# Supply.net
KiCad netlist of a schematic drawn in Altium Designer
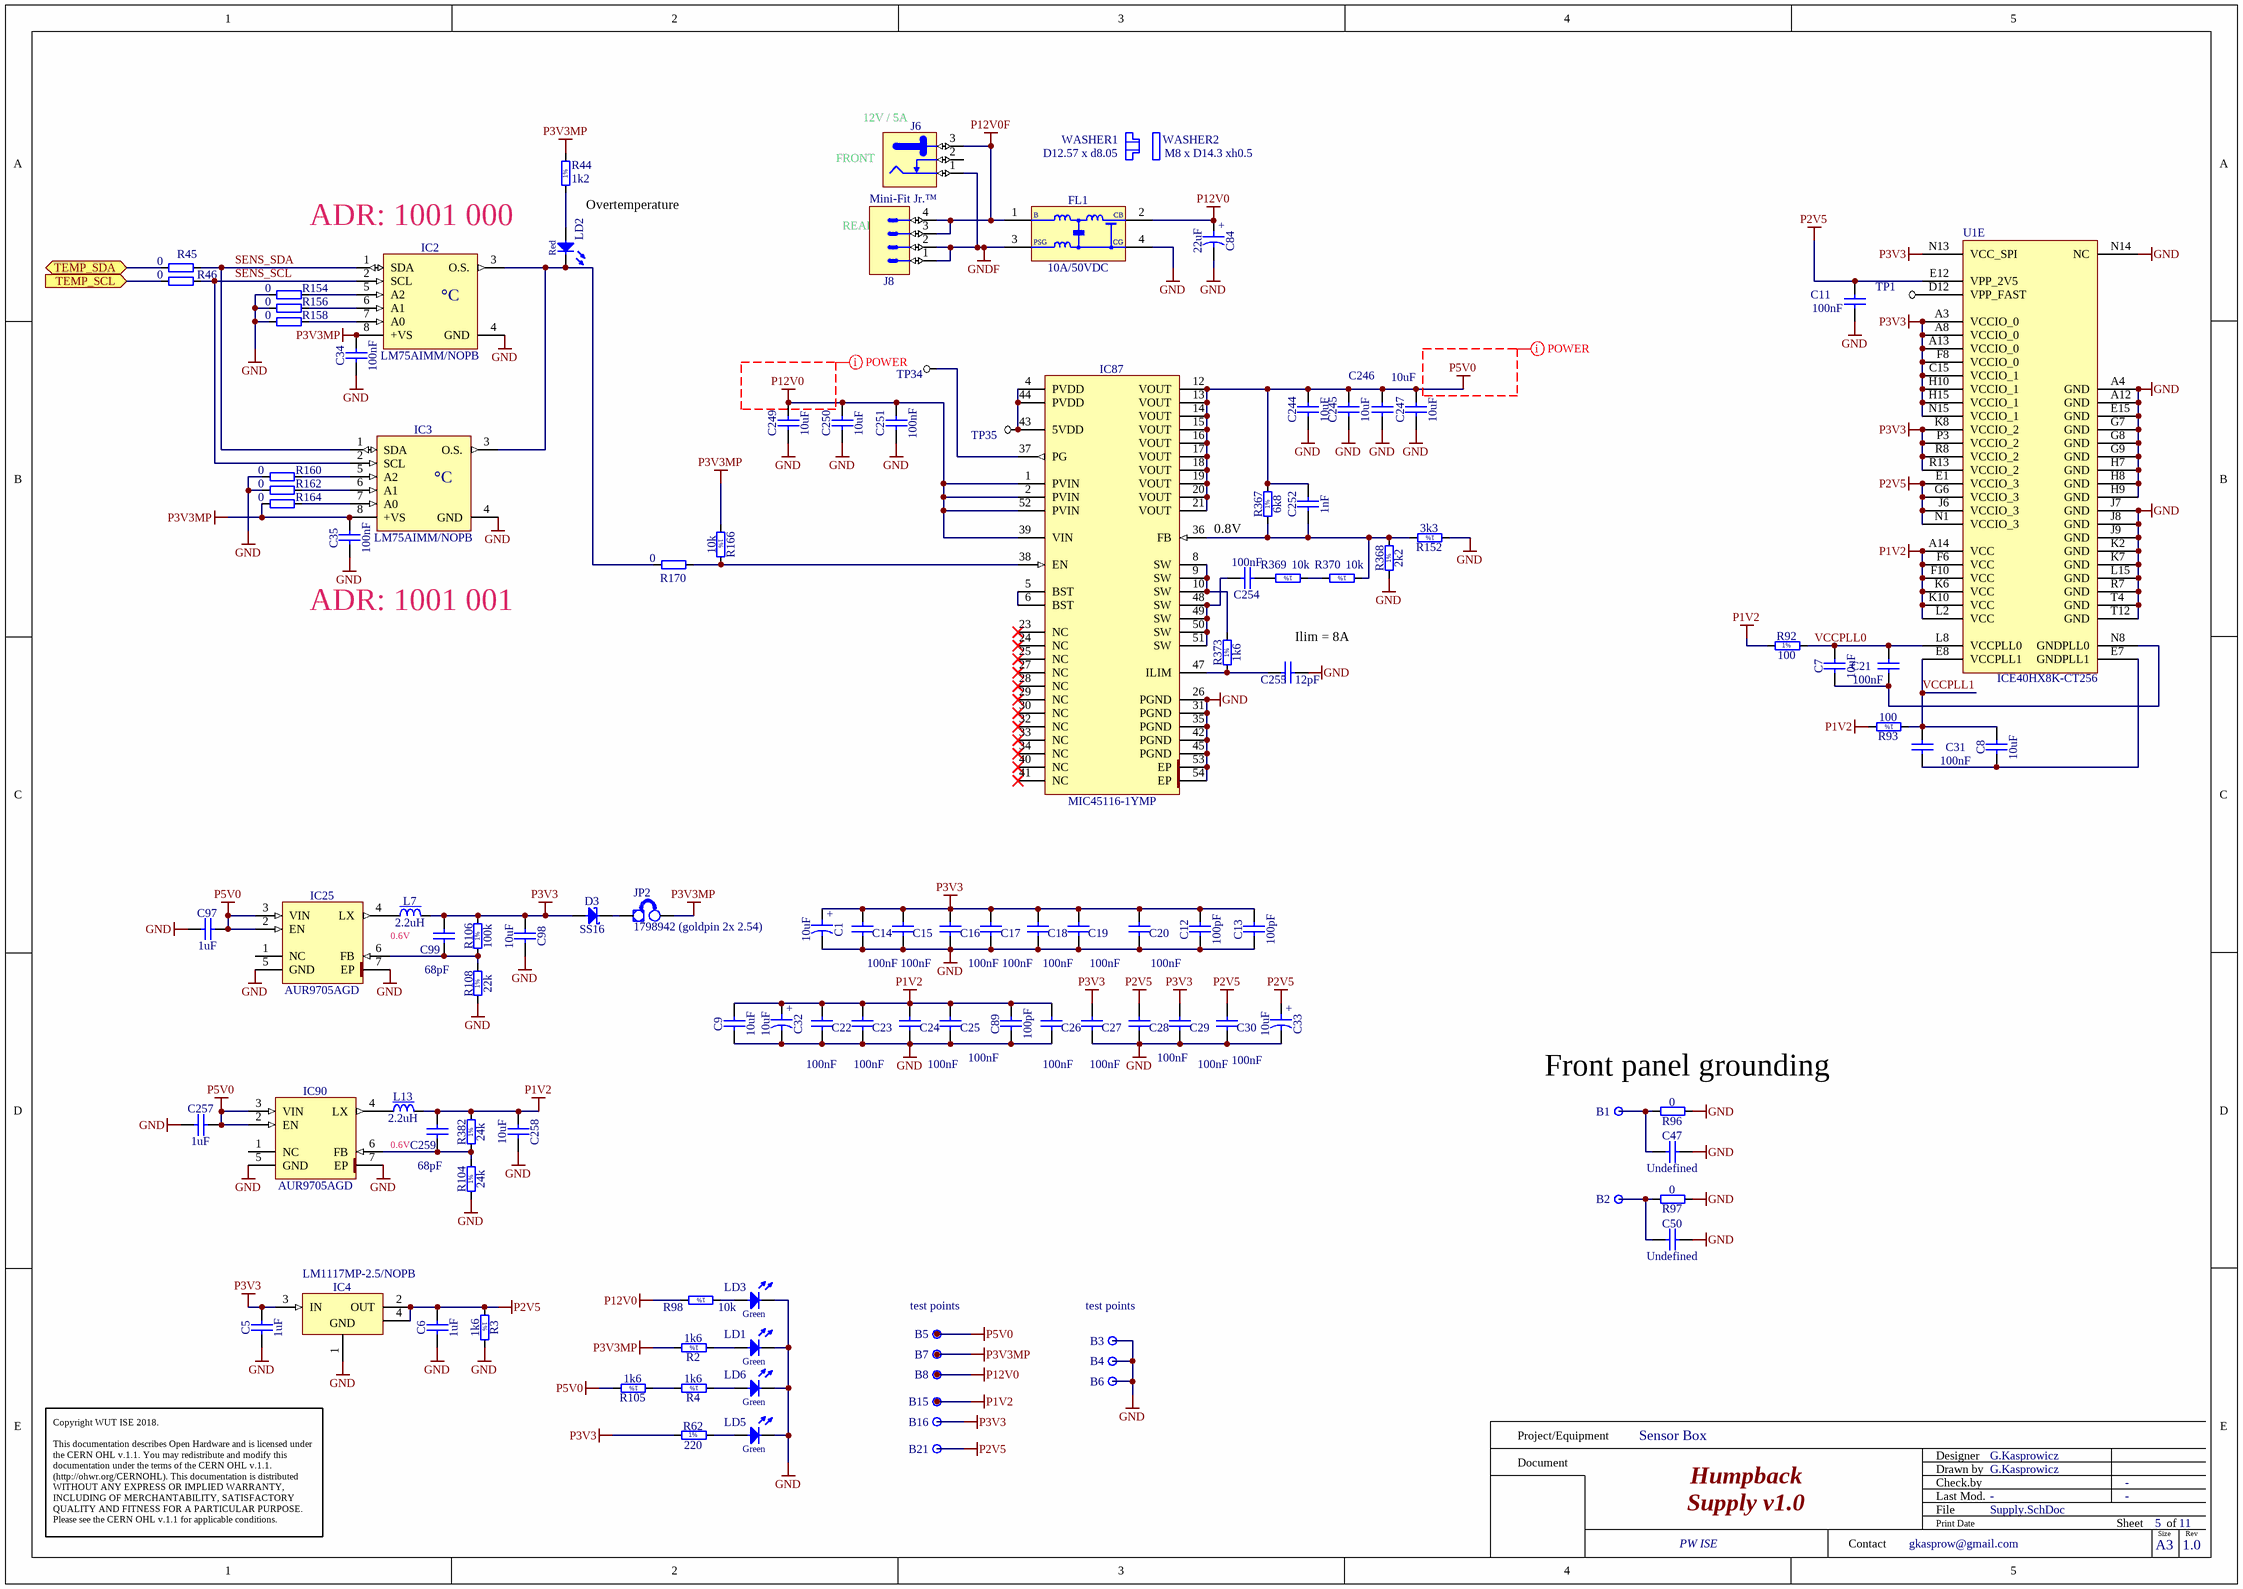
[diagram p0: Supply.SchDoc]

(export (version "E")
  (design (tool "Eeschema 10.0.6"))
  (components
    (comp (ref "B1")
      (value "Plated Hole")
      (footprint "MTG270_500")
      (description "Single Terminal Socket")
      (fields (field (name "PART NUMBER") "PLATED_HOLE2.7_PAD5.0") (field (name "AUTHOR") "CERN DEM JMW"))
      (libsource (lib "Eletro-mechanical") (part "Single Terminal Socket"))
    )
    (comp (ref "B2")
      (value "Plated Hole")
      (footprint "MTG270_500")
      (description "Single Terminal Socket")
      (fields (field (name "PART NUMBER") "PLATED_HOLE2.7_PAD5.0") (field (name "AUTHOR") "CERN DEM JMW"))
      (libsource (lib "Eletro-mechanical") (part "Single Terminal Socket"))
    )
    (comp (ref "B3")
      (value "Plated Hole")
      (footprint "c130h60")
      (description "Single Terminal Socket")
      (fields (field (name "PART NUMBER") "PLATED_HOLE0.6_PAD1.3") (field (name "AUTHOR") "CERN DEM MR"))
      (libsource (lib "Eletro-mechanical") (part "Single Terminal Socket"))
    )
    (comp (ref "B4")
      (value "Plated Hole")
      (footprint "c130h60")
      (description "Single Terminal Socket")
      (fields (field (name "PART NUMBER") "PLATED_HOLE0.6_PAD1.3") (field (name "AUTHOR") "CERN DEM MR"))
      (libsource (lib "Eletro-mechanical") (part "Single Terminal Socket"))
    )
    (comp (ref "B5")
      (value "Plated Hole")
      (footprint "c130h60")
      (description "Single Terminal Socket")
      (fields (field (name "PART NUMBER") "PLATED_HOLE0.6_PAD1.3") (field (name "AUTHOR") "CERN DEM MR"))
      (libsource (lib "Eletro-mechanical") (part "Single Terminal Socket"))
    )
    (comp (ref "B6")
      (value "Plated Hole")
      (footprint "c130h60")
      (description "Single Terminal Socket")
      (fields (field (name "PART NUMBER") "PLATED_HOLE0.6_PAD1.3") (field (name "AUTHOR") "CERN DEM MR"))
      (libsource (lib "Eletro-mechanical") (part "Single Terminal Socket"))
    )
    (comp (ref "B7")
      (value "Plated Hole")
      (footprint "c130h60")
      (description "Single Terminal Socket")
      (fields (field (name "PART NUMBER") "PLATED_HOLE0.6_PAD1.3") (field (name "AUTHOR") "CERN DEM MR"))
      (libsource (lib "Eletro-mechanical") (part "Single Terminal Socket"))
    )
    (comp (ref "B8")
      (value "Plated Hole")
      (footprint "c130h60")
      (description "Single Terminal Socket")
      (fields (field (name "PART NUMBER") "PLATED_HOLE0.6_PAD1.3") (field (name "AUTHOR") "CERN DEM MR"))
      (libsource (lib "Eletro-mechanical") (part "Single Terminal Socket"))
    )
    (comp (ref "B15")
      (value "Plated Hole")
      (footprint "c130h60")
      (description "Single Terminal Socket")
      (fields (field (name "PART NUMBER") "PLATED_HOLE0.6_PAD1.3") (field (name "AUTHOR") "CERN DEM MR"))
      (libsource (lib "Eletro-mechanical") (part "Single Terminal Socket"))
    )
    (comp (ref "B16")
      (value "Plated Hole")
      (footprint "c130h60")
      (description "Single Terminal Socket")
      (fields (field (name "PART NUMBER") "PLATED_HOLE0.6_PAD1.3") (field (name "AUTHOR") "CERN DEM MR"))
      (libsource (lib "Eletro-mechanical") (part "Single Terminal Socket"))
    )
    (comp (ref "B21")
      (value "Plated Hole")
      (footprint "c130h60")
      (description "Single Terminal Socket")
      (fields (field (name "PART NUMBER") "PLATED_HOLE0.6_PAD1.3") (field (name "AUTHOR") "CERN DEM MR"))
      (libsource (lib "Eletro-mechanical") (part "Single Terminal Socket"))
    )
    (comp (ref "C1")
      (value "10uF")
      (footprint "CAPAE430X540N")
      (description "Polarised capacitor")
      (fields
        (field (name "PART NUMBER") "CAE430-540_10UF_16V_20%")
        (field (name "VOLTAGE") "16V")
        (field (name "AUTHOR") "CERN DEM JLC")
      )
      (libsource (lib "Capacitors") (part "Capacitor - polarized"))
    )
    (comp (ref "C5")
      (value "1uF")
      (footprint "CAPC1608X87N")
      (description "Non-polarised capacitor")
      (fields
        (field (name "PART NUMBER") "CC0603_1UF_25V_10%_X7R")
        (field (name "VOLTAGE") "25V")
        (field (name "AUTHOR") "CERN DEM JLC")
      )
      (libsource (lib "Capacitors") (part "Capacitor - non polarized"))
    )
    (comp (ref "C6")
      (value "1uF")
      (footprint "CAPC1608X87N")
      (description "Non-polarised capacitor")
      (fields
        (field (name "PART NUMBER") "CC0603_1UF_25V_10%_X7R")
        (field (name "VOLTAGE") "25V")
        (field (name "AUTHOR") "CERN DEM JLC")
      )
      (libsource (lib "Capacitors") (part "Capacitor - non polarized"))
    )
    (comp (ref "C7")
      (value "10uF")
      (footprint "CAPC1005X70N")
      (description "Non-polarised capacitor")
      (fields
        (field (name "PART NUMBER") "CC0402_10UF_6.3V_20%_X5R")
        (field (name "VOLTAGE") "6.3V")
        (field (name "AUTHOR") "CERN DEM JLC")
      )
      (libsource (lib "Capacitors") (part "Capacitor - non polarized"))
    )
    (comp (ref "C8")
      (value "10uF")
      (footprint "CAPC1005X70N")
      (description "Non-polarised capacitor")
      (fields
        (field (name "PART NUMBER") "CC0402_10UF_6.3V_20%_X5R")
        (field (name "VOLTAGE") "6.3V")
        (field (name "AUTHOR") "CERN DEM JLC")
      )
      (libsource (lib "Capacitors") (part "Capacitor - non polarized"))
    )
    (comp (ref "C9")
      (value "10uF")
      (footprint "CAPC2012X135N")
      (description "Non-polarised capacitor")
      (fields
        (field (name "PART NUMBER") "CC0805_10UF_16V_10%_X5R")
        (field (name "VOLTAGE") "16V")
        (field (name "AUTHOR") "CERN DEM JLC")
      )
      (libsource (lib "Capacitors") (part "Capacitor - non polarized"))
    )
    (comp (ref "C11")
      (value "100nF")
      (footprint "CAPC1005X55N")
      (description "Non-polarised capacitor")
      (fields
        (field (name "PART NUMBER") "CC0402_100NF_16V_10%_X5R")
        (field (name "VOLTAGE") "16V")
        (field (name "AUTHOR") "CERN DEM JLC")
      )
      (libsource (lib "Capacitors") (part "Capacitor - non polarized"))
    )
    (comp (ref "C12")
      (value "100pF")
      (footprint "CAPC1608X87N")
      (description "Non-polarised capacitor")
      (fields
        (field (name "PART NUMBER") "CC0603_100PF_50V_10%_X7R")
        (field (name "VOLTAGE") "50V")
        (field (name "AUTHOR") "CERN DEM JLC")
      )
      (libsource (lib "Capacitors") (part "Capacitor - non polarized"))
    )
    (comp (ref "C13")
      (value "100pF")
      (footprint "CAPC1608X87N")
      (description "Non-polarised capacitor")
      (fields
        (field (name "PART NUMBER") "CC0603_100PF_50V_10%_X7R")
        (field (name "VOLTAGE") "50V")
        (field (name "AUTHOR") "CERN DEM JLC")
      )
      (libsource (lib "Capacitors") (part "Capacitor - non polarized"))
    )
    (comp (ref "C14")
      (value "100nF")
      (footprint "CAPC1005X55N")
      (description "Non-polarised capacitor")
      (fields
        (field (name "PART NUMBER") "CC0402_100NF_16V_10%_X5R")
        (field (name "VOLTAGE") "16V")
        (field (name "AUTHOR") "CERN DEM JLC")
      )
      (libsource (lib "Capacitors") (part "Capacitor - non polarized"))
    )
    (comp (ref "C15")
      (value "100nF")
      (footprint "CAPC1005X55N")
      (description "Non-polarised capacitor")
      (fields
        (field (name "PART NUMBER") "CC0402_100NF_16V_10%_X5R")
        (field (name "VOLTAGE") "16V")
        (field (name "AUTHOR") "CERN DEM JLC")
      )
      (libsource (lib "Capacitors") (part "Capacitor - non polarized"))
    )
    (comp (ref "C16")
      (value "100nF")
      (footprint "CAPC1005X55N")
      (description "Non-polarised capacitor")
      (fields
        (field (name "PART NUMBER") "CC0402_100NF_16V_10%_X5R")
        (field (name "VOLTAGE") "16V")
        (field (name "AUTHOR") "CERN DEM JLC")
      )
      (libsource (lib "Capacitors") (part "Capacitor - non polarized"))
    )
    (comp (ref "C17")
      (value "100nF")
      (footprint "CAPC1005X55N")
      (description "Non-polarised capacitor")
      (fields
        (field (name "PART NUMBER") "CC0402_100NF_16V_10%_X5R")
        (field (name "VOLTAGE") "16V")
        (field (name "AUTHOR") "CERN DEM JLC")
      )
      (libsource (lib "Capacitors") (part "Capacitor - non polarized"))
    )
    (comp (ref "C18")
      (value "100nF")
      (footprint "CAPC1005X55N")
      (description "Non-polarised capacitor")
      (fields
        (field (name "PART NUMBER") "CC0402_100NF_16V_10%_X5R")
        (field (name "VOLTAGE") "16V")
        (field (name "AUTHOR") "CERN DEM JLC")
      )
      (libsource (lib "Capacitors") (part "Capacitor - non polarized"))
    )
    (comp (ref "C19")
      (value "100nF")
      (footprint "CAPC1005X55N")
      (description "Non-polarised capacitor")
      (fields
        (field (name "PART NUMBER") "CC0402_100NF_16V_10%_X5R")
        (field (name "VOLTAGE") "16V")
        (field (name "AUTHOR") "CERN DEM JLC")
      )
      (libsource (lib "Capacitors") (part "Capacitor - non polarized"))
    )
    (comp (ref "C20")
      (value "100nF")
      (footprint "CAPC1005X55N")
      (description "Non-polarised capacitor")
      (fields
        (field (name "PART NUMBER") "CC0402_100NF_16V_10%_X5R")
        (field (name "VOLTAGE") "16V")
        (field (name "AUTHOR") "CERN DEM JLC")
      )
      (libsource (lib "Capacitors") (part "Capacitor - non polarized"))
    )
    (comp (ref "C21")
      (value "100nF")
      (footprint "CAPC1005X55N")
      (description "Non-polarised capacitor")
      (fields
        (field (name "PART NUMBER") "CC0402_100NF_16V_10%_X5R")
        (field (name "VOLTAGE") "16V")
        (field (name "AUTHOR") "CERN DEM JLC")
      )
      (libsource (lib "Capacitors") (part "Capacitor - non polarized"))
    )
    (comp (ref "C22")
      (value "100nF")
      (footprint "CAPC1005X55N")
      (description "Non-polarised capacitor")
      (fields
        (field (name "PART NUMBER") "CC0402_100NF_16V_10%_X5R")
        (field (name "VOLTAGE") "16V")
        (field (name "AUTHOR") "CERN DEM JLC")
      )
      (libsource (lib "Capacitors") (part "Capacitor - non polarized"))
    )
    (comp (ref "C23")
      (value "100nF")
      (footprint "CAPC1005X55N")
      (description "Non-polarised capacitor")
      (fields
        (field (name "PART NUMBER") "CC0402_100NF_16V_10%_X5R")
        (field (name "VOLTAGE") "16V")
        (field (name "AUTHOR") "CERN DEM JLC")
      )
      (libsource (lib "Capacitors") (part "Capacitor - non polarized"))
    )
    (comp (ref "C24")
      (value "100nF")
      (footprint "CAPC1005X55N")
      (description "Non-polarised capacitor")
      (fields
        (field (name "PART NUMBER") "CC0402_100NF_16V_10%_X5R")
        (field (name "VOLTAGE") "16V")
        (field (name "AUTHOR") "CERN DEM JLC")
      )
      (libsource (lib "Capacitors") (part "Capacitor - non polarized"))
    )
    (comp (ref "C25")
      (value "100nF")
      (footprint "CAPC1005X55N")
      (description "Non-polarised capacitor")
      (fields
        (field (name "PART NUMBER") "CC0402_100NF_16V_10%_X5R")
        (field (name "VOLTAGE") "16V")
        (field (name "AUTHOR") "CERN DEM JLC")
      )
      (libsource (lib "Capacitors") (part "Capacitor - non polarized"))
    )
    (comp (ref "C26")
      (value "100nF")
      (footprint "CAPC1005X55N")
      (description "Non-polarised capacitor")
      (fields
        (field (name "PART NUMBER") "CC0402_100NF_16V_10%_X5R")
        (field (name "VOLTAGE") "16V")
        (field (name "AUTHOR") "CERN DEM JLC")
      )
      (libsource (lib "Capacitors") (part "Capacitor - non polarized"))
    )
    (comp (ref "C27")
      (value "100nF")
      (footprint "CAPC1005X55N")
      (description "Non-polarised capacitor")
      (fields
        (field (name "PART NUMBER") "CC0402_100NF_16V_10%_X5R")
        (field (name "VOLTAGE") "16V")
        (field (name "AUTHOR") "CERN DEM JLC")
      )
      (libsource (lib "Capacitors") (part "Capacitor - non polarized"))
    )
    (comp (ref "C28")
      (value "100nF")
      (footprint "CAPC1005X55N")
      (description "Non-polarised capacitor")
      (fields
        (field (name "PART NUMBER") "CC0402_100NF_16V_10%_X5R")
        (field (name "VOLTAGE") "16V")
        (field (name "AUTHOR") "CERN DEM JLC")
      )
      (libsource (lib "Capacitors") (part "Capacitor - non polarized"))
    )
    (comp (ref "C29")
      (value "100nF")
      (footprint "CAPC1005X55N")
      (description "Non-polarised capacitor")
      (fields
        (field (name "PART NUMBER") "CC0402_100NF_16V_10%_X5R")
        (field (name "VOLTAGE") "16V")
        (field (name "AUTHOR") "CERN DEM JLC")
      )
      (libsource (lib "Capacitors") (part "Capacitor - non polarized"))
    )
    (comp (ref "C30")
      (value "100nF")
      (footprint "CAPC1005X55N")
      (description "Non-polarised capacitor")
      (fields
        (field (name "PART NUMBER") "CC0402_100NF_16V_10%_X5R")
        (field (name "VOLTAGE") "16V")
        (field (name "AUTHOR") "CERN DEM JLC")
      )
      (libsource (lib "Capacitors") (part "Capacitor - non polarized"))
    )
    (comp (ref "C31")
      (value "100nF")
      (footprint "CAPC1005X55N")
      (description "Non-polarised capacitor")
      (fields
        (field (name "PART NUMBER") "CC0402_100NF_16V_10%_X5R")
        (field (name "VOLTAGE") "16V")
        (field (name "AUTHOR") "CERN DEM JLC")
      )
      (libsource (lib "Capacitors") (part "Capacitor - non polarized"))
    )
    (comp (ref "C32")
      (value "10uF")
      (footprint "CAPAE430X540N")
      (description "Polarised capacitor")
      (fields
        (field (name "PART NUMBER") "CAE430-540_10UF_16V_20%")
        (field (name "VOLTAGE") "16V")
        (field (name "AUTHOR") "CERN DEM JLC")
      )
      (libsource (lib "Capacitors") (part "Capacitor - polarized"))
    )
    (comp (ref "C33")
      (value "10uF")
      (footprint "CAPAE430X540N")
      (description "Polarised capacitor")
      (fields
        (field (name "PART NUMBER") "CAE430-540_10UF_16V_20%")
        (field (name "VOLTAGE") "16V")
        (field (name "AUTHOR") "CERN DEM JLC")
      )
      (libsource (lib "Capacitors") (part "Capacitor - polarized"))
    )
    (comp (ref "C34")
      (value "100nF")
      (footprint "CAPC1005X55N")
      (description "Non-polarised capacitor")
      (fields
        (field (name "PART NUMBER") "CC0402_100NF_16V_10%_X5R")
        (field (name "VOLTAGE") "16V")
        (field (name "AUTHOR") "CERN DEM JLC")
      )
      (libsource (lib "Capacitors") (part "Capacitor - non polarized"))
    )
    (comp (ref "C35")
      (value "100nF")
      (footprint "CAPC1005X55N")
      (description "Non-polarised capacitor")
      (fields
        (field (name "PART NUMBER") "CC0402_100NF_16V_10%_X5R")
        (field (name "VOLTAGE") "16V")
        (field (name "AUTHOR") "CERN DEM JLC")
      )
      (libsource (lib "Capacitors") (part "Capacitor - non polarized"))
    )
    (comp (ref "C47")
      (value "Undefined")
      (footprint "CAPC2012X135N")
      (description "Non-polarised capacitor")
      (fields (field (name "PART NUMBER") "CC0805_NO-VALUE") (field (name "AUTHOR") "CERN DEM JLC"))
      (libsource (lib "Capacitors") (part "Capacitor - non polarized"))
    )
    (comp (ref "C50")
      (value "Undefined")
      (footprint "CAPC2012X135N")
      (description "Non-polarised capacitor")
      (fields (field (name "PART NUMBER") "CC0805_NO-VALUE") (field (name "AUTHOR") "CERN DEM JLC"))
      (libsource (lib "Capacitors") (part "Capacitor - non polarized"))
    )
    (comp (ref "C84")
      (value "22uF")
      (footprint "CAPAE530X540N")
      (description "Polarised capacitor")
      (fields
        (field (name "PART NUMBER") "CAE530-540_22UF_16V_20%")
        (field (name "VOLTAGE") "16V")
        (field (name "AUTHOR") "CERN DEM JLC")
      )
      (libsource (lib "Capacitors") (part "Capacitor - polarized"))
    )
    (comp (ref "C89")
      (value "100pF")
      (footprint "CAPC1608X87N")
      (description "Non-polarised capacitor")
      (fields
        (field (name "PART NUMBER") "CC0603_100PF_50V_10%_X7R")
        (field (name "VOLTAGE") "50V")
        (field (name "AUTHOR") "CERN DEM JLC")
      )
      (libsource (lib "Capacitors") (part "Capacitor - non polarized"))
    )
    (comp (ref "C97")
      (value "1uF")
      (footprint "CAPC1005X55N")
      (description "Non-polarised capacitor")
      (fields
        (field (name "PART NUMBER") "CC0402_1UF_16V_10%_X5R")
        (field (name "VOLTAGE") "16V")
        (field (name "AUTHOR") "CERN DEM JLC")
      )
      (libsource (lib "Capacitors") (part "Capacitor - non polarized"))
    )
    (comp (ref "C98")
      (value "10uF")
      (footprint "CAPC2012X135N")
      (description "Non-polarised capacitor")
      (fields
        (field (name "PART NUMBER") "CC0805_10UF_16V_10%_X5R")
        (field (name "VOLTAGE") "16V")
        (field (name "AUTHOR") "CERN DEM JLC")
      )
      (libsource (lib "Capacitors") (part "Capacitor - non polarized"))
    )
    (comp (ref "C99")
      (value "68pF")
      (footprint "CAPC1608X87N")
      (description "Non-polarised capacitor")
      (fields
        (field (name "PART NUMBER") "CC0603_68PF_50V_5%_NP0")
        (field (name "VOLTAGE") "50V")
        (field (name "AUTHOR") "CERN DEM JLC")
      )
      (libsource (lib "Capacitors") (part "Capacitor - non polarized"))
    )
    (comp (ref "C244")
      (value "10uF")
      (footprint "CAPC2012X135N")
      (description "Non-polarised capacitor")
      (fields
        (field (name "PART NUMBER") "CC0805_10UF_16V_10%_X5R")
        (field (name "VOLTAGE") "16V")
        (field (name "AUTHOR") "CERN DEM JLC")
      )
      (libsource (lib "Capacitors") (part "Capacitor - non polarized"))
    )
    (comp (ref "C245")
      (value "10uF")
      (footprint "CAPC2012X135N")
      (description "Non-polarised capacitor")
      (fields
        (field (name "PART NUMBER") "CC0805_10UF_16V_10%_X5R")
        (field (name "VOLTAGE") "16V")
        (field (name "AUTHOR") "CERN DEM JLC")
      )
      (libsource (lib "Capacitors") (part "Capacitor - non polarized"))
    )
    (comp (ref "C246")
      (value "10uF")
      (footprint "CAPC2012X135N")
      (description "Non-polarised capacitor")
      (fields
        (field (name "PART NUMBER") "CC0805_10UF_16V_10%_X5R")
        (field (name "VOLTAGE") "16V")
        (field (name "AUTHOR") "CERN DEM JLC")
      )
      (libsource (lib "Capacitors") (part "Capacitor - non polarized"))
    )
    (comp (ref "C247")
      (value "10uF")
      (footprint "CAPC2012X135N")
      (description "Non-polarised capacitor")
      (fields
        (field (name "PART NUMBER") "CC0805_10UF_16V_10%_X5R")
        (field (name "VOLTAGE") "16V")
        (field (name "AUTHOR") "CERN DEM JLC")
      )
      (libsource (lib "Capacitors") (part "Capacitor - non polarized"))
    )
    (comp (ref "C249")
      (value "10uF")
      (footprint "CAPC2012X135N")
      (description "Non-polarised capacitor")
      (fields
        (field (name "PART NUMBER") "CC0805_10UF_16V_10%_X5R")
        (field (name "VOLTAGE") "16V")
        (field (name "AUTHOR") "CERN DEM JLC")
      )
      (libsource (lib "Capacitors") (part "Capacitor - non polarized"))
    )
    (comp (ref "C250")
      (value "10uF")
      (footprint "CAPC2012X135N")
      (description "Non-polarised capacitor")
      (fields
        (field (name "PART NUMBER") "CC0805_10UF_16V_10%_X5R")
        (field (name "VOLTAGE") "16V")
        (field (name "AUTHOR") "CERN DEM JLC")
      )
      (libsource (lib "Capacitors") (part "Capacitor - non polarized"))
    )
    (comp (ref "C251")
      (value "100nF")
      (footprint "CAPC1005X55N")
      (description "Non-polarised capacitor")
      (fields
        (field (name "PART NUMBER") "CC0402_100NF_16V_10%_X5R")
        (field (name "VOLTAGE") "16V")
        (field (name "AUTHOR") "CERN DEM JLC")
      )
      (libsource (lib "Capacitors") (part "Capacitor - non polarized"))
    )
    (comp (ref "C252")
      (value "1nF")
      (footprint "CAPC1608X87N")
      (description "Non-polarised capacitor")
      (fields
        (field (name "PART NUMBER") "CC0603_1NF_100V_10%_X7R")
        (field (name "VOLTAGE") "100V")
        (field (name "AUTHOR") "CERN DEM JLC")
      )
      (libsource (lib "Capacitors") (part "Capacitor - non polarized"))
    )
    (comp (ref "C254")
      (value "100nF")
      (footprint "CAPC1005X55N")
      (description "Non-polarised capacitor")
      (fields
        (field (name "PART NUMBER") "CC0402_100NF_16V_10%_X5R")
        (field (name "VOLTAGE") "16V")
        (field (name "AUTHOR") "CERN DEM JLC")
      )
      (libsource (lib "Capacitors") (part "Capacitor - non polarized"))
    )
    (comp (ref "C255")
      (value "12pF")
      (footprint "CAPC1005X55N")
      (description "Non-polarised capacitor")
      (fields
        (field (name "PART NUMBER") "CC0402_12PF_50V_5%_C0G")
        (field (name "VOLTAGE") "50V")
        (field (name "AUTHOR") "CERN DEM JLC")
      )
      (libsource (lib "Capacitors") (part "Capacitor - non polarized"))
    )
    (comp (ref "C257")
      (value "1uF")
      (footprint "CAPC1005X55N")
      (description "Non-polarised capacitor")
      (fields
        (field (name "PART NUMBER") "CC0402_1UF_16V_10%_X5R")
        (field (name "VOLTAGE") "16V")
        (field (name "AUTHOR") "CERN DEM JLC")
      )
      (libsource (lib "Capacitors") (part "Capacitor - non polarized"))
    )
    (comp (ref "C258")
      (value "10uF")
      (footprint "CAPC2012X135N")
      (description "Non-polarised capacitor")
      (fields
        (field (name "PART NUMBER") "CC0805_10UF_16V_10%_X5R")
        (field (name "VOLTAGE") "16V")
        (field (name "AUTHOR") "CERN DEM JLC")
      )
      (libsource (lib "Capacitors") (part "Capacitor - non polarized"))
    )
    (comp (ref "C259")
      (value "68pF")
      (footprint "CAPC1608X87N")
      (description "Non-polarised capacitor")
      (fields
        (field (name "PART NUMBER") "CC0603_68PF_50V_5%_NP0")
        (field (name "VOLTAGE") "50V")
        (field (name "AUTHOR") "CERN DEM JLC")
      )
      (libsource (lib "Capacitors") (part "Capacitor - non polarized"))
    )
    (comp (ref "D3")
      (value "SS16")
      (footprint "DIOM5127X229N")
      (description "Schottky Diode")
      (fields
        (field (name "VOLTAGE") "60V")
        (field (name "POWER") "1A")
        (field (name "AUTHOR") "CERN DEM JLC")
      )
      (libsource (lib "ICs And Semiconductors") (part "Diode Schottky"))
    )
    (comp (ref "FL1")
      (value "10A/50VDC")
      (footprint "FIL_MURATA_BNX02")
      (description "Block Type EMIFIL (LC Combined)")
      (fields
        (field (name "PART NUMBER") "FIL_MURATA_BNX022-01L")
        (field (name "MANUFACTURER") "MURATA")
        (field (name "AUTHOR") "CERN DEM JLC")
      )
      (libsource (lib "Inductors & Transformers") (part "FIL_MURATA_BNX02"))
    )
    (comp (ref "IC2")
      (value "LM75AIMM/NOPB")
      (footprint "SOP65P490X109-8N")
      (description "Digital Temperature Sensor and Thermal Watchdog with Two-Wire Interface")
      (fields (field (name "MANUFACTURER") "TEXAS INSTRUMENTS") (field (name "AUTHOR") "CERN DEM JLC"))
      (libsource (lib "ICs And Semiconductors") (part "LM75"))
    )
    (comp (ref "IC3")
      (value "LM75AIMM/NOPB")
      (footprint "SOP65P490X109-8N")
      (description "Digital Temperature Sensor and Thermal Watchdog with Two-Wire Interface")
      (fields (field (name "MANUFACTURER") "TEXAS INSTRUMENTS") (field (name "AUTHOR") "CERN DEM JLC"))
      (libsource (lib "ICs And Semiconductors") (part "LM75"))
    )
    (comp (ref "IC4")
      (value "LM1117MP-2.5/NOPB")
      (footprint "SOT230P700X180-4N")
      (description "3-Terminal Regulator 1=GND 2=OUT 3=IN 4=OUT")
      (fields (field (name "MANUFACTURER") "TEXAS INSTRUMENTS") (field (name "AUTHOR") "CERN DEM JLC"))
      (libsource (lib "ICs And Semiconductors") (part "REG3+1 1GND-2OUT-3IN+4OUT"))
    )
    (comp (ref "IC25")
      (value "AUR9705AGD")
      (footprint "SON65P200X200X80-7N-R65X145")
      (description "0V to 6V Input, 1A, 1.5MHz, Step-Down DC-DC Converter")
      (fields (field (name "MANUFACTURER") "DIODES INCORPORATED") (field (name "AUTHOR") "CERN DEM MR"))
      (libsource (lib "ICs And Semiconductors") (part "AUR9705AGD"))
    )
    (comp (ref "IC87")
      (value "MIC45116-1YMP")
      (footprint "MICROCHIP_H3QFN88-52LD-PL-3")
      (description "0.8V to 85% PVIN (4.75-19V), 6A Synchronous Step-Down Regulator Module")
      (fields (field (name "MANUFACTURER") "MICROCHIP TECHNOLOGY") (field (name "AUTHOR") "CERN DEM JMW"))
      (libsource (lib "ICs And Semiconductors") (part "MIC45116"))
    )
    (comp (ref "IC90")
      (value "AUR9705AGD")
      (footprint "SON65P200X200X80-7N-R65X145")
      (description "0V to 6V Input, 1A, 1.5MHz, Step-Down DC-DC Converter")
      (fields (field (name "MANUFACTURER") "DIODES INCORPORATED") (field (name "AUTHOR") "CERN DEM MR"))
      (libsource (lib "ICs And Semiconductors") (part "AUR9705AGD"))
    )
    (comp (ref "J6")
      (value "Jack")
      (footprint "SWITCHCRAFT_L712RA")
      (description "24V /3. 5A, 2.1mm Diameter Pin, SMD DC Power Supply Connector With  Break Contact")
      (fields
        (field (name "PART NUMBER") "SWITCHCRAFT_L712RA")
        (field (name "MANUFACTURER") "SWITCHCRAFT")
        (field (name "AUTHOR") "GK")
      )
      (libsource (lib "LIBRARY_SCH") (part "CON_DC_5A_THT_RA"))
    )
    (comp (ref "J8")
      (value "Mini-Fit Jr.™")
      (footprint "MOLEX_39-30-0040")
      (description "Connector 4 Male")
      (fields
        (field (name "PART NUMBER") "MOLEX_39-30-0040")
        (field (name "FAMILY") "Mini-Fit Jr.™")
        (field (name "MANUFACTURER") "MOLEX")
        (field (name "AUTHOR") "CERN DEM JLC")
      )
      (libsource (lib "Connectors") (part "Connector 4 Male"))
    )
    (comp (ref "JP2")
      (value "1798942 (goldpin 2x 2.54)")
      (footprint "jump")
      (description "Jumper")
      (libsource (lib "LIBRARY_SCH") (part "JUMPER"))
    )
    (comp (ref "L7")
      (value "2.2uH")
      (footprint "IND_MURATA_LQH44PN_P0")
      (description "Inductor With Core")
      (fields
        (field (name "PART NUMBER") "IND_2.2UH_20%_MURATA_LQH44PN2R2MP0L")
        (field (name "POWER") "1.8A")
        (field (name "AUTHOR") "CERN DEM JLC")
      )
      (libsource (lib "Inductors & Transformers") (part "Inductor With Magnetic core"))
    )
    (comp (ref "L13")
      (value "2.2uH")
      (footprint "IND_MURATA_LQH44PN_P0")
      (description "Inductor With Core")
      (fields
        (field (name "PART NUMBER") "IND_2.2UH_20%_MURATA_LQH44PN2R2MP0L")
        (field (name "POWER") "1.8A")
        (field (name "AUTHOR") "CERN DEM JLC")
      )
      (libsource (lib "Inductors & Transformers") (part "Inductor With Magnetic core"))
    )
    (comp (ref "LD1")
      (value "Green")
      (footprint "LED_KINGBRIGHT_KPH-1608CGCK")
      (description "LED Green 1C 2A")
      (fields
        (field (name "PART NUMBER") "LED_KINGBRIGHT_KPH-1608CGCK")
        (field (name "MANUFACTURER") "KINGBRIGHT")
        (field (name "AUTHOR") "CERN DEM JLC")
      )
      (libsource (lib "ICs And Semiconductors") (part "LED Green 1C 2A"))
    )
    (comp (ref "LD2")
      (value "Red")
      (footprint "LED_AVAGO_HSMC-C120")
      (description "LED Red 1C 2A")
      (fields
        (field (name "PART NUMBER") "LED_AVAGO_HSMC-C120")
        (field (name "MANUFACTURER") "AVAGO TECHNOLOGIES")
        (field (name "AUTHOR") "CERN DEM JMW")
      )
      (libsource (lib "ICs And Semiconductors") (part "LED Red 1C 2A"))
    )
    (comp (ref "LD3")
      (value "Green")
      (footprint "LED_KINGBRIGHT_KPH-1608CGCK")
      (description "LED Green 1C 2A")
      (fields
        (field (name "PART NUMBER") "LED_KINGBRIGHT_KPH-1608CGCK")
        (field (name "MANUFACTURER") "KINGBRIGHT")
        (field (name "AUTHOR") "CERN DEM JLC")
      )
      (libsource (lib "ICs And Semiconductors") (part "LED Green 1C 2A"))
    )
    (comp (ref "LD5")
      (value "Green")
      (footprint "LED_KINGBRIGHT_KPH-1608CGCK")
      (description "LED Green 1C 2A")
      (fields
        (field (name "PART NUMBER") "LED_KINGBRIGHT_KPH-1608CGCK")
        (field (name "MANUFACTURER") "KINGBRIGHT")
        (field (name "AUTHOR") "CERN DEM JLC")
      )
      (libsource (lib "ICs And Semiconductors") (part "LED Green 1C 2A"))
    )
    (comp (ref "LD6")
      (value "Green")
      (footprint "LED_KINGBRIGHT_KPH-1608CGCK")
      (description "LED Green 1C 2A")
      (fields
        (field (name "PART NUMBER") "LED_KINGBRIGHT_KPH-1608CGCK")
        (field (name "MANUFACTURER") "KINGBRIGHT")
        (field (name "AUTHOR") "CERN DEM JLC")
      )
      (libsource (lib "ICs And Semiconductors") (part "LED Green 1C 2A"))
    )
    (comp (ref "R2")
      (value "1k6")
      (footprint "RESC1005X40N")
      (description "Resistor - 1%")
      (fields
        (field (name "PART NUMBER") "R0402_1K6_1%_0.0625W_100PPM")
        (field (name "POWER") "0.0625W")
        (field (name "AUTHOR") "CERN DEM JLC")
      )
      (libsource (lib "Resistors") (part "Resistor - 1%"))
    )
    (comp (ref "R3")
      (value "1k6")
      (footprint "RESC1005X40N")
      (description "Resistor - 1%")
      (fields
        (field (name "PART NUMBER") "R0402_1K6_1%_0.0625W_100PPM")
        (field (name "POWER") "0.0625W")
        (field (name "AUTHOR") "CERN DEM JLC")
      )
      (libsource (lib "Resistors") (part "Resistor - 1%"))
    )
    (comp (ref "R4")
      (value "1k6")
      (footprint "RESC1005X40N")
      (description "Resistor - 1%")
      (fields
        (field (name "PART NUMBER") "R0402_1K6_1%_0.0625W_100PPM")
        (field (name "POWER") "0.0625W")
        (field (name "AUTHOR") "CERN DEM JLC")
      )
      (libsource (lib "Resistors") (part "Resistor - 1%"))
    )
    (comp (ref "R44")
      (value "1k2")
      (footprint "RESC1608X55N")
      (description "Resistor - 1%")
      (fields
        (field (name "PART NUMBER") "R0603_1K2_1%_0.1W_100PPM")
        (field (name "POWER") "0.1W")
        (field (name "AUTHOR") "CERN DEM JLC")
      )
      (libsource (lib "Resistors") (part "Resistor - 1%"))
    )
    (comp (ref "R45")
      (value "0")
      (footprint "RESC1005X40N")
      (description "Resistor")
      (fields
        (field (name "PART NUMBER") "R0402_0R_JUMPER")
        (field (name "MANUFACTURER") "GENERIC")
        (field (name "AUTHOR") "CERN DEM JLC")
      )
      (libsource (lib "Resistors") (part "Resistor"))
    )
    (comp (ref "R46")
      (value "0")
      (footprint "RESC1005X40N")
      (description "Resistor")
      (fields
        (field (name "PART NUMBER") "R0402_0R_JUMPER")
        (field (name "MANUFACTURER") "GENERIC")
        (field (name "AUTHOR") "CERN DEM JLC")
      )
      (libsource (lib "Resistors") (part "Resistor"))
    )
    (comp (ref "R62")
      (value "220")
      (footprint "RESC1608X55N")
      (description "Resistor - 1%")
      (fields
        (field (name "PART NUMBER") "R0603_220R_1%_0.1W_100PPM")
        (field (name "POWER") "0.1W")
        (field (name "AUTHOR") "CERN DEM JLC")
      )
      (libsource (lib "Resistors") (part "Resistor - 1%"))
    )
    (comp (ref "R92")
      (value "100")
      (footprint "RESC1005X40N")
      (description "Resistor - 1%")
      (fields
        (field (name "PART NUMBER") "R0402_100R_1%_0.0625W_100PPM")
        (field (name "POWER") "0.0625W")
        (field (name "AUTHOR") "CERN DEM JLC")
      )
      (libsource (lib "Resistors") (part "Resistor - 1%"))
    )
    (comp (ref "R93")
      (value "100")
      (footprint "RESC1005X40N")
      (description "Resistor - 1%")
      (fields
        (field (name "PART NUMBER") "R0402_100R_1%_0.0625W_100PPM")
        (field (name "POWER") "0.0625W")
        (field (name "AUTHOR") "CERN DEM JLC")
      )
      (libsource (lib "Resistors") (part "Resistor - 1%"))
    )
    (comp (ref "R96")
      (value "0")
      (footprint "RESC1608X55N")
      (description "Resistor")
      (fields
        (field (name "PART NUMBER") "R0603_0R_JUMPER")
        (field (name "MANUFACTURER") "GENERIC")
        (field (name "AUTHOR") "CERN DEM JLC")
      )
      (libsource (lib "Resistors") (part "Resistor"))
    )
    (comp (ref "R97")
      (value "0")
      (footprint "RESC1608X55N")
      (description "Resistor")
      (fields
        (field (name "PART NUMBER") "R0603_0R_JUMPER")
        (field (name "MANUFACTURER") "GENERIC")
        (field (name "AUTHOR") "CERN DEM JLC")
      )
      (libsource (lib "Resistors") (part "Resistor"))
    )
    (comp (ref "R98")
      (value "10k")
      (footprint "RESC1005X40N")
      (description "Resistor - 1%")
      (fields
        (field (name "PART NUMBER") "R0402_10K_1%_0.0625W_100PPM")
        (field (name "POWER") "0.0625W")
        (field (name "AUTHOR") "CERN DEM JLC")
      )
      (libsource (lib "Resistors") (part "Resistor - 1%"))
    )
    (comp (ref "R104")
      (value "24k")
      (footprint "RESC1005X40N")
      (description "Resistor - 1%")
      (fields
        (field (name "PART NUMBER") "R0402_24K_1%_0.0625W_100PPM")
        (field (name "POWER") "0.0625W")
        (field (name "AUTHOR") "CERN DEM JLC")
      )
      (libsource (lib "Resistors") (part "Resistor - 1%"))
    )
    (comp (ref "R105")
      (value "1k6")
      (footprint "RESC1005X40N")
      (description "Resistor - 1%")
      (fields
        (field (name "PART NUMBER") "R0402_1K6_1%_0.0625W_100PPM")
        (field (name "POWER") "0.0625W")
        (field (name "AUTHOR") "CERN DEM JLC")
      )
      (libsource (lib "Resistors") (part "Resistor - 1%"))
    )
    (comp (ref "R106")
      (value "100k")
      (footprint "RESC1005X40N")
      (description "Resistor - 1%")
      (fields
        (field (name "PART NUMBER") "R0402_100K_1%_0.0625W_100PPM")
        (field (name "POWER") "0.0625W")
        (field (name "AUTHOR") "CERN DEM JLC")
      )
      (libsource (lib "Resistors") (part "Resistor - 1%"))
    )
    (comp (ref "R108")
      (value "22k")
      (footprint "RESC1005X40N")
      (description "Resistor - 1%")
      (fields
        (field (name "PART NUMBER") "R0402_22K_1%_0.0625W_100PPM")
        (field (name "POWER") "0.0625W")
        (field (name "AUTHOR") "CERN DEM JLC")
      )
      (libsource (lib "Resistors") (part "Resistor - 1%"))
    )
    (comp (ref "R152")
      (value "3k3")
      (footprint "RESC1005X40N")
      (description "Resistor - 1%")
      (fields
        (field (name "PART NUMBER") "R0402_3K3_1%_0.0625W_100PPM")
        (field (name "POWER") "0.0625W")
        (field (name "AUTHOR") "CERN DEM JLC")
      )
      (libsource (lib "Resistors") (part "Resistor - 1%"))
    )
    (comp (ref "R154")
      (value "0")
      (footprint "RESC1005X40N")
      (description "Resistor")
      (fields
        (field (name "PART NUMBER") "R0402_0R_JUMPER")
        (field (name "MANUFACTURER") "GENERIC")
        (field (name "AUTHOR") "CERN DEM JLC")
      )
      (libsource (lib "Resistors") (part "Resistor"))
    )
    (comp (ref "R156")
      (value "0")
      (footprint "RESC1005X40N")
      (description "Resistor")
      (fields
        (field (name "PART NUMBER") "R0402_0R_JUMPER")
        (field (name "MANUFACTURER") "GENERIC")
        (field (name "AUTHOR") "CERN DEM JLC")
      )
      (libsource (lib "Resistors") (part "Resistor"))
    )
    (comp (ref "R158")
      (value "0")
      (footprint "RESC1005X40N")
      (description "Resistor")
      (fields
        (field (name "PART NUMBER") "R0402_0R_JUMPER")
        (field (name "MANUFACTURER") "GENERIC")
        (field (name "AUTHOR") "CERN DEM JLC")
      )
      (libsource (lib "Resistors") (part "Resistor"))
    )
    (comp (ref "R160")
      (value "0")
      (footprint "RESC1005X40N")
      (description "Resistor")
      (fields
        (field (name "PART NUMBER") "R0402_0R_JUMPER")
        (field (name "MANUFACTURER") "GENERIC")
        (field (name "AUTHOR") "CERN DEM JLC")
      )
      (libsource (lib "Resistors") (part "Resistor"))
    )
    (comp (ref "R162")
      (value "0")
      (footprint "RESC1005X40N")
      (description "Resistor")
      (fields
        (field (name "PART NUMBER") "R0402_0R_JUMPER")
        (field (name "MANUFACTURER") "GENERIC")
        (field (name "AUTHOR") "CERN DEM JLC")
      )
      (libsource (lib "Resistors") (part "Resistor"))
    )
    (comp (ref "R164")
      (value "0")
      (footprint "RESC1005X40N")
      (description "Resistor")
      (fields
        (field (name "PART NUMBER") "R0402_0R_JUMPER")
        (field (name "MANUFACTURER") "GENERIC")
        (field (name "AUTHOR") "CERN DEM JLC")
      )
      (libsource (lib "Resistors") (part "Resistor"))
    )
    (comp (ref "R166")
      (value "10k")
      (footprint "RESC1005X40N")
      (description "Resistor - 1%")
      (fields
        (field (name "PART NUMBER") "R0402_10K_1%_0.0625W_100PPM")
        (field (name "POWER") "0.0625W")
        (field (name "AUTHOR") "CERN DEM JLC")
      )
      (libsource (lib "Resistors") (part "Resistor - 1%"))
    )
    (comp (ref "R170")
      (value "0")
      (footprint "RESC1005X40N")
      (description "Resistor")
      (fields
        (field (name "PART NUMBER") "R0402_0R_JUMPER")
        (field (name "MANUFACTURER") "GENERIC")
        (field (name "AUTHOR") "CERN DEM JLC")
      )
      (libsource (lib "Resistors") (part "Resistor"))
    )
    (comp (ref "R367")
      (value "6k8")
      (footprint "RESC1005X40N")
      (description "Resistor - 1%")
      (fields
        (field (name "PART NUMBER") "R0402_6K8_1%_0.0625W_100PPM")
        (field (name "POWER") "0.0625W")
        (field (name "AUTHOR") "CERN DEM JLC")
      )
      (libsource (lib "Resistors") (part "Resistor - 1%"))
    )
    (comp (ref "R368")
      (value "2k2")
      (footprint "RESC1608X55N")
      (description "Resistor - 1%")
      (fields
        (field (name "PART NUMBER") "R0603_2K2_1%_0.1W_100PPM")
        (field (name "POWER") "0.1W")
        (field (name "AUTHOR") "CERN DEM JLC")
      )
      (libsource (lib "Resistors") (part "Resistor - 1%"))
    )
    (comp (ref "R369")
      (value "10k")
      (footprint "RESC1005X40N")
      (description "Resistor - 1%")
      (fields
        (field (name "PART NUMBER") "R0402_10K_1%_0.0625W_100PPM")
        (field (name "POWER") "0.0625W")
        (field (name "AUTHOR") "CERN DEM JLC")
      )
      (libsource (lib "Resistors") (part "Resistor - 1%"))
    )
    (comp (ref "R370")
      (value "10k")
      (footprint "RESC1005X40N")
      (description "Resistor - 1%")
      (fields
        (field (name "PART NUMBER") "R0402_10K_1%_0.0625W_100PPM")
        (field (name "POWER") "0.0625W")
        (field (name "AUTHOR") "CERN DEM JLC")
      )
      (libsource (lib "Resistors") (part "Resistor - 1%"))
    )
    (comp (ref "R373")
      (value "1k6")
      (footprint "RESC1005X40N")
      (description "Resistor - 1%")
      (fields
        (field (name "PART NUMBER") "R0402_1K6_1%_0.0625W_100PPM")
        (field (name "POWER") "0.0625W")
        (field (name "AUTHOR") "CERN DEM JLC")
      )
      (libsource (lib "Resistors") (part "Resistor - 1%"))
    )
    (comp (ref "R382")
      (value "24k")
      (footprint "RESC1005X40N")
      (description "Resistor - 1%")
      (fields
        (field (name "PART NUMBER") "R0402_24K_1%_0.0625W_100PPM")
        (field (name "POWER") "0.0625W")
        (field (name "AUTHOR") "CERN DEM JLC")
      )
      (libsource (lib "Resistors") (part "Resistor - 1%"))
    )
    (comp (ref "TP1")
      (value "TP")
      (footprint "TP")
      (description "Testpoint")
      (libsource (lib "LIBRARY_SCH") (part "TP"))
    )
    (comp (ref "TP34")
      (value "TP")
      (footprint "TP")
      (description "Testpoint")
      (libsource (lib "LIBRARY_SCH") (part "TP"))
    )
    (comp (ref "TP35")
      (value "TP")
      (footprint "TP")
      (description "Testpoint")
      (libsource (lib "LIBRARY_SCH") (part "TP"))
    )
    (comp (ref "U1")
      (value "ICE40HX8K-CT256")
      (footprint "LATC-caBGA-256")
      (fields (field (name "MANUFACTURER") "Lattice Semiconductor"))
      (libsource (lib "Altium Content Vault") (part "LATC-HX8K-caBGA-256"))
    )
    (comp (ref "WASHER1")
      (value "D12.57 x d8.05")
      (footprint "Washer_s4263")
      (description "8mm_Shoulder Washer")
      (fields
        (field (name "PART NUMBER") "Switchcraft_s4263")
        (field (name "MANUFACTURER") "Switchcraft")
        (field (name "AUTHOR") "GK")
      )
      (libsource (lib "LIBRARY_SCH") (part "MECH_Washer_s4263"))
    )
    (comp (ref "WASHER2")
      (value "M8 x D14.3 xh0.5")
      (footprint "Washer_M8x0.5x14.3")
      (description "M8 x0.5x14.3 Nylon Washer")
      (fields
        (field (name "PART NUMBER") "WS-M 8-0.5(14.3)")
        (field (name "MANUFACTURER") "ADSYS ELEMENTY")
        (field (name "AUTHOR") "GK")
      )
      (libsource (lib "LIBRARY_SCH") (part "MECH_Washer_M8x0.5x14.3"))
    )
  )
  (nets
    (net (code "1") (name "/SENS_SCL") (class "Default")
      (node (ref "IC2") (pin "2") (pinfunction "SCL_2") (pintype "input"))
      (node (ref "IC3") (pin "2") (pinfunction "SCL_2") (pintype "input"))
      (node (ref "R46") (pin "2") (pinfunction "2_2") (pintype "passive"))
    )
    (net (code "2") (name "/SENS_SDA") (class "Default")
      (node (ref "IC2") (pin "1") (pinfunction "SDA_1") (pintype "bidirectional"))
      (node (ref "IC3") (pin "1") (pinfunction "SDA_1") (pintype "bidirectional"))
      (node (ref "R45") (pin "2") (pinfunction "2_2") (pintype "passive"))
    )
    (net (code "3") (name "/TEMP_SCL") (class "Default")
      (node (ref "R46") (pin "1") (pinfunction "1_1") (pintype "passive"))
    )
    (net (code "4") (name "/TEMP_SDA") (class "Default")
      (node (ref "R45") (pin "1") (pinfunction "1_1") (pintype "passive"))
    )
    (net (code "5") (name "/VCCPLL0") (class "Default")
      (node (ref "C21") (pin "2") (pinfunction "2_2") (pintype "passive"))
      (node (ref "C7") (pin "2") (pinfunction "2_2") (pintype "passive"))
      (node (ref "R92") (pin "2") (pinfunction "2_2") (pintype "passive"))
      (node (ref "U1") (pin "L8") (pinfunction "VCCPLL0_L8") (pintype "power_in"))
    )
    (net (code "6") (name "/VCCPLL1") (class "Default")
      (node (ref "C31") (pin "2") (pinfunction "2_2") (pintype "passive"))
      (node (ref "C8") (pin "2") (pinfunction "2_2") (pintype "passive"))
      (node (ref "R93") (pin "1") (pinfunction "1_1") (pintype "passive"))
      (node (ref "U1") (pin "E8") (pinfunction "VCCPLL1_E8") (pintype "power_in"))
    )
    (net (code "7") (name "GND") (class "Default")
      (node (ref "B3") (pin "1") (pinfunction "1_1") (pintype "bidirectional"))
      (node (ref "B4") (pin "1") (pinfunction "1_1") (pintype "bidirectional"))
      (node (ref "B6") (pin "1") (pinfunction "1_1") (pintype "bidirectional"))
      (node (ref "C1") (pin "2") (pinfunction "2_2") (pintype "passive"))
      (node (ref "C11") (pin "1") (pinfunction "1_1") (pintype "passive"))
      (node (ref "C12") (pin "1") (pinfunction "1_1") (pintype "passive"))
      (node (ref "C13") (pin "1") (pinfunction "1_1") (pintype "passive"))
      (node (ref "C14") (pin "1") (pinfunction "1_1") (pintype "passive"))
      (node (ref "C15") (pin "1") (pinfunction "1_1") (pintype "passive"))
      (node (ref "C16") (pin "1") (pinfunction "1_1") (pintype "passive"))
      (node (ref "C17") (pin "1") (pinfunction "1_1") (pintype "passive"))
      (node (ref "C18") (pin "1") (pinfunction "1_1") (pintype "passive"))
      (node (ref "C19") (pin "1") (pinfunction "1_1") (pintype "passive"))
      (node (ref "C20") (pin "1") (pinfunction "1_1") (pintype "passive"))
      (node (ref "C22") (pin "1") (pinfunction "1_1") (pintype "passive"))
      (node (ref "C23") (pin "1") (pinfunction "1_1") (pintype "passive"))
      (node (ref "C24") (pin "1") (pinfunction "1_1") (pintype "passive"))
      (node (ref "C244") (pin "1") (pinfunction "1_1") (pintype "passive"))
      (node (ref "C245") (pin "1") (pinfunction "1_1") (pintype "passive"))
      (node (ref "C246") (pin "1") (pinfunction "1_1") (pintype "passive"))
      (node (ref "C247") (pin "1") (pinfunction "1_1") (pintype "passive"))
      (node (ref "C249") (pin "1") (pinfunction "1_1") (pintype "passive"))
      (node (ref "C25") (pin "1") (pinfunction "1_1") (pintype "passive"))
      (node (ref "C250") (pin "1") (pinfunction "1_1") (pintype "passive"))
      (node (ref "C251") (pin "1") (pinfunction "1_1") (pintype "passive"))
      (node (ref "C255") (pin "1") (pinfunction "1_1") (pintype "passive"))
      (node (ref "C257") (pin "1") (pinfunction "1_1") (pintype "passive"))
      (node (ref "C258") (pin "2") (pinfunction "2_2") (pintype "passive"))
      (node (ref "C26") (pin "1") (pinfunction "1_1") (pintype "passive"))
      (node (ref "C27") (pin "1") (pinfunction "1_1") (pintype "passive"))
      (node (ref "C28") (pin "1") (pinfunction "1_1") (pintype "passive"))
      (node (ref "C29") (pin "1") (pinfunction "1_1") (pintype "passive"))
      (node (ref "C30") (pin "1") (pinfunction "1_1") (pintype "passive"))
      (node (ref "C32") (pin "2") (pinfunction "2_2") (pintype "passive"))
      (node (ref "C33") (pin "2") (pinfunction "2_2") (pintype "passive"))
      (node (ref "C34") (pin "1") (pinfunction "1_1") (pintype "passive"))
      (node (ref "C35") (pin "1") (pinfunction "1_1") (pintype "passive"))
      (node (ref "C47") (pin "2") (pinfunction "2_2") (pintype "passive"))
      (node (ref "C5") (pin "1") (pinfunction "1_1") (pintype "passive"))
      (node (ref "C50") (pin "2") (pinfunction "2_2") (pintype "passive"))
      (node (ref "C6") (pin "1") (pinfunction "1_1") (pintype "passive"))
      (node (ref "C84") (pin "2") (pinfunction "2_2") (pintype "passive"))
      (node (ref "C89") (pin "1") (pinfunction "1_1") (pintype "passive"))
      (node (ref "C9") (pin "1") (pinfunction "1_1") (pintype "passive"))
      (node (ref "C97") (pin "1") (pinfunction "1_1") (pintype "passive"))
      (node (ref "C98") (pin "2") (pinfunction "2_2") (pintype "passive"))
      (node (ref "FL1") (pin "4") (pinfunction "CG_4") (pintype "passive"))
      (node (ref "IC2") (pin "4") (pinfunction "GND_4") (pintype "power_in"))
      (node (ref "IC25") (pin "5") (pinfunction "GND_5") (pintype "power_in"))
      (node (ref "IC25") (pin "7") (pinfunction "EP_7") (pintype "passive"))
      (node (ref "IC3") (pin "4") (pinfunction "GND_4") (pintype "power_in"))
      (node (ref "IC4") (pin "1") (pinfunction "GND_1") (pintype "power_in"))
      (node (ref "IC87") (pin "26") (pinfunction "PGND_26") (pintype "power_in"))
      (node (ref "IC87") (pin "31") (pinfunction "PGND_31") (pintype "power_in"))
      (node (ref "IC87") (pin "35") (pinfunction "PGND_35") (pintype "power_in"))
      (node (ref "IC87") (pin "42") (pinfunction "PGND_42") (pintype "power_in"))
      (node (ref "IC87") (pin "45") (pinfunction "PGND_45") (pintype "power_in"))
      (node (ref "IC87") (pin "53") (pinfunction "EP_53") (pintype "power_in"))
      (node (ref "IC87") (pin "54") (pinfunction "EP_54") (pintype "power_in"))
      (node (ref "IC90") (pin "5") (pinfunction "GND_5") (pintype "power_in"))
      (node (ref "IC90") (pin "7") (pinfunction "EP_7") (pintype "passive"))
      (node (ref "LD1") (pin "1") (pinfunction "C_1") (pintype "passive"))
      (node (ref "LD3") (pin "1") (pinfunction "C_1") (pintype "passive"))
      (node (ref "LD5") (pin "1") (pinfunction "C_1") (pintype "passive"))
      (node (ref "LD6") (pin "1") (pinfunction "C_1") (pintype "passive"))
      (node (ref "R104") (pin "1") (pinfunction "1_1") (pintype "passive"))
      (node (ref "R108") (pin "1") (pinfunction "1_1") (pintype "passive"))
      (node (ref "R152") (pin "1") (pinfunction "1_1") (pintype "passive"))
      (node (ref "R154") (pin "1") (pinfunction "1_1") (pintype "passive"))
      (node (ref "R156") (pin "1") (pinfunction "1_1") (pintype "passive"))
      (node (ref "R158") (pin "1") (pinfunction "1_1") (pintype "passive"))
      (node (ref "R160") (pin "1") (pinfunction "1_1") (pintype "passive"))
      (node (ref "R162") (pin "1") (pinfunction "1_1") (pintype "passive"))
      (node (ref "R3") (pin "2") (pinfunction "2_2") (pintype "passive"))
      (node (ref "R368") (pin "1") (pinfunction "1_1") (pintype "passive"))
      (node (ref "R96") (pin "1") (pinfunction "1_1") (pintype "passive"))
      (node (ref "R97") (pin "1") (pinfunction "1_1") (pintype "passive"))
      (node (ref "U1") (pin "A12") (pinfunction "GND_A12") (pintype "power_in"))
      (node (ref "U1") (pin "A4") (pinfunction "GND_A4") (pintype "power_in"))
      (node (ref "U1") (pin "E15") (pinfunction "GND_E15") (pintype "power_in"))
      (node (ref "U1") (pin "G7") (pinfunction "GND_G7") (pintype "power_in"))
      (node (ref "U1") (pin "G8") (pinfunction "GND_G8") (pintype "power_in"))
      (node (ref "U1") (pin "G9") (pinfunction "GND_G9") (pintype "power_in"))
      (node (ref "U1") (pin "H7") (pinfunction "GND_H7") (pintype "power_in"))
      (node (ref "U1") (pin "H8") (pinfunction "GND_H8") (pintype "power_in"))
      (node (ref "U1") (pin "H9") (pinfunction "GND_H9") (pintype "power_in"))
      (node (ref "U1") (pin "J7") (pinfunction "GND_J7") (pintype "power_in"))
      (node (ref "U1") (pin "J8") (pinfunction "GND_J8") (pintype "power_in"))
      (node (ref "U1") (pin "J9") (pinfunction "GND_J9") (pintype "power_in"))
      (node (ref "U1") (pin "K2") (pinfunction "GND_K2") (pintype "power_in"))
      (node (ref "U1") (pin "K7") (pinfunction "GND_K7") (pintype "power_in"))
      (node (ref "U1") (pin "L15") (pinfunction "GND_L15") (pintype "power_in"))
      (node (ref "U1") (pin "N14") (pinfunction "NC_N14") (pintype "passive"))
      (node (ref "U1") (pin "R7") (pinfunction "GND_R7") (pintype "power_in"))
      (node (ref "U1") (pin "T12") (pinfunction "GND_T12") (pintype "power_in"))
      (node (ref "U1") (pin "T4") (pinfunction "GND_T4") (pintype "power_in"))
    )
    (net (code "8") (name "GNDF") (class "Default")
      (node (ref "FL1") (pin "3") (pinfunction "PSG_3") (pintype "passive"))
      (node (ref "J6") (pin "1") (pinfunction "1_1") (pintype "bidirectional"))
      (node (ref "J8") (pin "1") (pinfunction "1_1") (pintype "bidirectional"))
      (node (ref "J8") (pin "2") (pinfunction "2_2") (pintype "bidirectional"))
    )
    (net (code "9") (name "Net-(B1-Pad1)") (class "Default")
      (node (ref "B1") (pin "1") (pinfunction "1_1") (pintype "bidirectional"))
      (node (ref "C47") (pin "1") (pinfunction "1_1") (pintype "passive"))
      (node (ref "R96") (pin "2") (pinfunction "2_2") (pintype "passive"))
    )
    (net (code "10") (name "Net-(B2-Pad1)") (class "Default")
      (node (ref "B2") (pin "1") (pinfunction "1_1") (pintype "bidirectional"))
      (node (ref "C50") (pin "1") (pinfunction "1_1") (pintype "passive"))
      (node (ref "R97") (pin "2") (pinfunction "2_2") (pintype "passive"))
    )
    (net (code "11") (name "Net-(C254-Pad1)") (class "Default")
      (node (ref "C254") (pin "1") (pinfunction "1_1") (pintype "passive"))
      (node (ref "R369") (pin "2") (pinfunction "2_2") (pintype "passive"))
    )
    (net (code "12") (name "Net-(C254-Pad2)") (class "Default")
      (node (ref "C254") (pin "2") (pinfunction "2_2") (pintype "passive"))
      (node (ref "IC87") (pin "48") (pinfunction "SW_48") (pintype "passive"))
      (node (ref "IC87") (pin "49") (pinfunction "SW_49") (pintype "passive"))
      (node (ref "IC87") (pin "50") (pinfunction "SW_50") (pintype "passive"))
      (node (ref "IC87") (pin "51") (pinfunction "SW_51") (pintype "passive"))
    )
    (net (code "13") (name "Net-(D3-C)") (class "Default")
      (node (ref "D3") (pin "1") (pinfunction "C_1") (pintype "passive"))
      (node (ref "JP2") (pin "1") (pinfunction "E1_1") (pintype "passive"))
    )
    (net (code "14") (name "Net-(IC2-A0)") (class "Default")
      (node (ref "IC2") (pin "7") (pinfunction "A0_7") (pintype "input"))
      (node (ref "R158") (pin "2") (pinfunction "2_2") (pintype "passive"))
    )
    (net (code "15") (name "Net-(IC2-A1)") (class "Default")
      (node (ref "IC2") (pin "6") (pinfunction "A1_6") (pintype "input"))
      (node (ref "R156") (pin "2") (pinfunction "2_2") (pintype "passive"))
    )
    (net (code "16") (name "Net-(IC2-A2)") (class "Default")
      (node (ref "IC2") (pin "5") (pinfunction "A2_5") (pintype "input"))
      (node (ref "R154") (pin "2") (pinfunction "2_2") (pintype "passive"))
    )
    (net (code "17") (name "Net-(IC2-O.S.)") (class "Default")
      (node (ref "IC2") (pin "3") (pinfunction "O.S._3") (pintype "output"))
      (node (ref "IC3") (pin "3") (pinfunction "O.S._3") (pintype "output"))
      (node (ref "LD2") (pin "1") (pinfunction "C_1") (pintype "passive"))
      (node (ref "R170") (pin "1") (pinfunction "1_1") (pintype "passive"))
    )
    (net (code "18") (name "Net-(IC3-A0)") (class "Default")
      (node (ref "IC3") (pin "7") (pinfunction "A0_7") (pintype "input"))
      (node (ref "R164") (pin "2") (pinfunction "2_2") (pintype "passive"))
    )
    (net (code "19") (name "Net-(IC3-A1)") (class "Default")
      (node (ref "IC3") (pin "6") (pinfunction "A1_6") (pintype "input"))
      (node (ref "R162") (pin "2") (pinfunction "2_2") (pintype "passive"))
    )
    (net (code "20") (name "Net-(IC3-A2)") (class "Default")
      (node (ref "IC3") (pin "5") (pinfunction "A2_5") (pintype "input"))
      (node (ref "R160") (pin "2") (pinfunction "2_2") (pintype "passive"))
    )
    (net (code "21") (name "Net-(IC25-FB)") (class "Default")
      (node (ref "C99") (pin "1") (pinfunction "1_1") (pintype "passive"))
      (node (ref "IC25") (pin "6") (pinfunction "FB_6") (pintype "input"))
      (node (ref "R106") (pin "1") (pinfunction "1_1") (pintype "passive"))
      (node (ref "R108") (pin "2") (pinfunction "2_2") (pintype "passive"))
    )
    (net (code "22") (name "Net-(IC25-LX)") (class "Default")
      (node (ref "IC25") (pin "4") (pinfunction "LX_4") (pintype "output"))
      (node (ref "L7") (pin "1") (pinfunction "1_1") (pintype "passive"))
    )
    (net (code "23") (name "Net-(IC87-5VDD)") (class "Default")
      (node (ref "IC87") (pin "4") (pinfunction "PVDD_4") (pintype "power_in"))
      (node (ref "IC87") (pin "43") (pinfunction "5VDD_43") (pintype "power_in"))
      (node (ref "IC87") (pin "44") (pinfunction "PVDD_44") (pintype "power_in"))
      (node (ref "TP35") (pin "1") (pintype "passive"))
    )
    (net (code "24") (name "Net-(IC87-BST-Pad5)") (class "Default")
      (node (ref "IC87") (pin "5") (pinfunction "BST_5") (pintype "passive"))
      (node (ref "IC87") (pin "6") (pinfunction "BST_6") (pintype "passive"))
    )
    (net (code "25") (name "Net-(IC87-EN)") (class "Default")
      (node (ref "IC87") (pin "38") (pinfunction "EN_38") (pintype "input"))
      (node (ref "R166") (pin "2") (pinfunction "2_2") (pintype "passive"))
      (node (ref "R170") (pin "2") (pinfunction "2_2") (pintype "passive"))
    )
    (net (code "26") (name "Net-(IC87-FB)") (class "Default")
      (node (ref "C252") (pin "1") (pinfunction "1_1") (pintype "passive"))
      (node (ref "IC87") (pin "36") (pinfunction "FB_36") (pintype "input"))
      (node (ref "R152") (pin "2") (pinfunction "2_2") (pintype "passive"))
      (node (ref "R367") (pin "1") (pinfunction "1_1") (pintype "passive"))
      (node (ref "R368") (pin "2") (pinfunction "2_2") (pintype "passive"))
      (node (ref "R370") (pin "1") (pinfunction "1_1") (pintype "passive"))
    )
    (net (code "27") (name "Net-(IC87-ILIM)") (class "Default")
      (node (ref "C255") (pin "2") (pinfunction "2_2") (pintype "passive"))
      (node (ref "IC87") (pin "47") (pinfunction "ILIM_47") (pintype "passive"))
      (node (ref "R373") (pin "1") (pinfunction "1_1") (pintype "passive"))
    )
    (net (code "28") (name "Net-(IC87-PG)") (class "Default")
      (node (ref "IC87") (pin "37") (pinfunction "PG_37") (pintype "output"))
      (node (ref "TP34") (pin "1") (pintype "passive"))
    )
    (net (code "29") (name "Net-(IC87-SW-Pad10)") (class "Default")
      (node (ref "IC87") (pin "10") (pinfunction "SW_10") (pintype "passive"))
      (node (ref "IC87") (pin "8") (pinfunction "SW_8") (pintype "passive"))
      (node (ref "IC87") (pin "9") (pinfunction "SW_9") (pintype "passive"))
      (node (ref "R373") (pin "2") (pinfunction "2_2") (pintype "passive"))
    )
    (net (code "30") (name "Net-(IC90-FB)") (class "Default")
      (node (ref "C259") (pin "1") (pinfunction "1_1") (pintype "passive"))
      (node (ref "IC90") (pin "6") (pinfunction "FB_6") (pintype "input"))
      (node (ref "R104") (pin "2") (pinfunction "2_2") (pintype "passive"))
      (node (ref "R382") (pin "1") (pinfunction "1_1") (pintype "passive"))
    )
    (net (code "31") (name "Net-(IC90-LX)") (class "Default")
      (node (ref "IC90") (pin "4") (pinfunction "LX_4") (pintype "output"))
      (node (ref "L13") (pin "1") (pinfunction "1_1") (pintype "passive"))
    )
    (net (code "32") (name "Net-(LD1-A)") (class "Default")
      (node (ref "LD1") (pin "2") (pinfunction "A_2") (pintype "passive"))
      (node (ref "R2") (pin "1") (pinfunction "1_1") (pintype "passive"))
    )
    (net (code "33") (name "Net-(LD2-A)") (class "Default")
      (node (ref "LD2") (pin "2") (pinfunction "A_2") (pintype "passive"))
      (node (ref "R44") (pin "1") (pinfunction "1_1") (pintype "passive"))
    )
    (net (code "34") (name "Net-(LD3-A)") (class "Default")
      (node (ref "LD3") (pin "2") (pinfunction "A_2") (pintype "passive"))
      (node (ref "R98") (pin "1") (pinfunction "1_1") (pintype "passive"))
    )
    (net (code "35") (name "Net-(LD5-A)") (class "Default")
      (node (ref "LD5") (pin "2") (pinfunction "A_2") (pintype "passive"))
      (node (ref "R62") (pin "2") (pinfunction "2_2") (pintype "passive"))
    )
    (net (code "36") (name "Net-(LD6-A)") (class "Default")
      (node (ref "LD6") (pin "2") (pinfunction "A_2") (pintype "passive"))
      (node (ref "R4") (pin "1") (pinfunction "1_1") (pintype "passive"))
    )
    (net (code "37") (name "Net-(R105-Pad1)") (class "Default")
      (node (ref "R105") (pin "1") (pinfunction "1_1") (pintype "passive"))
      (node (ref "R4") (pin "2") (pinfunction "2_2") (pintype "passive"))
    )
    (net (code "38") (name "Net-(R369-Pad1)") (class "Default")
      (node (ref "R369") (pin "1") (pinfunction "1_1") (pintype "passive"))
      (node (ref "R370") (pin "2") (pinfunction "2_2") (pintype "passive"))
    )
    (net (code "39") (name "Net-(U1E-GNDPLL0)") (class "Default")
      (node (ref "C21") (pin "1") (pinfunction "1_1") (pintype "passive"))
      (node (ref "C7") (pin "1") (pinfunction "1_1") (pintype "passive"))
      (node (ref "U1") (pin "N8") (pinfunction "GNDPLL0_N8") (pintype "power_in"))
    )
    (net (code "40") (name "Net-(U1E-GNDPLL1)") (class "Default")
      (node (ref "C31") (pin "1") (pinfunction "1_1") (pintype "passive"))
      (node (ref "C8") (pin "1") (pinfunction "1_1") (pintype "passive"))
      (node (ref "U1") (pin "E7") (pinfunction "GNDPLL1_E7") (pintype "power_in"))
    )
    (net (code "41") (name "Net-(U1E-VPP_FAST)") (class "Default")
      (node (ref "TP1") (pin "1") (pintype "passive"))
      (node (ref "U1") (pin "D12") (pinfunction "VPP_FAST_D12") (pintype "power_in"))
    )
    (net (code "42") (name "P1V2") (class "Default")
      (node (ref "B15") (pin "1") (pinfunction "1_1") (pintype "bidirectional"))
      (node (ref "C22") (pin "2") (pinfunction "2_2") (pintype "passive"))
      (node (ref "C23") (pin "2") (pinfunction "2_2") (pintype "passive"))
      (node (ref "C24") (pin "2") (pinfunction "2_2") (pintype "passive"))
      (node (ref "C25") (pin "2") (pinfunction "2_2") (pintype "passive"))
      (node (ref "C258") (pin "1") (pinfunction "1_1") (pintype "passive"))
      (node (ref "C259") (pin "2") (pinfunction "2_2") (pintype "passive"))
      (node (ref "C26") (pin "2") (pinfunction "2_2") (pintype "passive"))
      (node (ref "C32") (pin "1") (pinfunction "1_1") (pintype "passive"))
      (node (ref "C89") (pin "2") (pinfunction "2_2") (pintype "passive"))
      (node (ref "C9") (pin "2") (pinfunction "2_2") (pintype "passive"))
      (node (ref "L13") (pin "2") (pinfunction "2_2") (pintype "passive"))
      (node (ref "R382") (pin "2") (pinfunction "2_2") (pintype "passive"))
      (node (ref "R92") (pin "1") (pinfunction "1_1") (pintype "passive"))
      (node (ref "R93") (pin "2") (pinfunction "2_2") (pintype "passive"))
      (node (ref "U1") (pin "A14") (pinfunction "VCC_A14") (pintype "power_in"))
      (node (ref "U1") (pin "F10") (pinfunction "VCC_F10") (pintype "power_in"))
      (node (ref "U1") (pin "F6") (pinfunction "VCC_F6") (pintype "power_in"))
      (node (ref "U1") (pin "K10") (pinfunction "VCC_K10") (pintype "power_in"))
      (node (ref "U1") (pin "K6") (pinfunction "VCC_K6") (pintype "power_in"))
      (node (ref "U1") (pin "L2") (pinfunction "VCC_L2") (pintype "power_in"))
    )
    (net (code "43") (name "P2V5") (class "Default")
      (node (ref "B21") (pin "1") (pinfunction "1_1") (pintype "bidirectional"))
      (node (ref "C11") (pin "2") (pinfunction "2_2") (pintype "passive"))
      (node (ref "C28") (pin "2") (pinfunction "2_2") (pintype "passive"))
      (node (ref "C30") (pin "2") (pinfunction "2_2") (pintype "passive"))
      (node (ref "C33") (pin "1") (pinfunction "1_1") (pintype "passive"))
      (node (ref "C6") (pin "2") (pinfunction "2_2") (pintype "passive"))
      (node (ref "IC4") (pin "2") (pinfunction "OUT_2") (pintype "power_in"))
      (node (ref "IC4") (pin "4") (pinfunction "OUT_4") (pintype "power_in"))
      (node (ref "R3") (pin "1") (pinfunction "1_1") (pintype "passive"))
      (node (ref "U1") (pin "E1") (pinfunction "VCCIO_3_E1") (pintype "power_in"))
      (node (ref "U1") (pin "E12") (pinfunction "VPP_2V5_E12") (pintype "power_in"))
      (node (ref "U1") (pin "G6") (pinfunction "VCCIO_3_G6") (pintype "power_in"))
      (node (ref "U1") (pin "J6") (pinfunction "VCCIO_3_J6") (pintype "power_in"))
      (node (ref "U1") (pin "N1") (pinfunction "VCCIO_3_N1") (pintype "power_in"))
    )
    (net (code "44") (name "P3V3") (class "Default")
      (node (ref "B16") (pin "1") (pinfunction "1_1") (pintype "bidirectional"))
      (node (ref "C1") (pin "1") (pinfunction "1_1") (pintype "passive"))
      (node (ref "C12") (pin "2") (pinfunction "2_2") (pintype "passive"))
      (node (ref "C13") (pin "2") (pinfunction "2_2") (pintype "passive"))
      (node (ref "C14") (pin "2") (pinfunction "2_2") (pintype "passive"))
      (node (ref "C15") (pin "2") (pinfunction "2_2") (pintype "passive"))
      (node (ref "C16") (pin "2") (pinfunction "2_2") (pintype "passive"))
      (node (ref "C17") (pin "2") (pinfunction "2_2") (pintype "passive"))
      (node (ref "C18") (pin "2") (pinfunction "2_2") (pintype "passive"))
      (node (ref "C19") (pin "2") (pinfunction "2_2") (pintype "passive"))
      (node (ref "C20") (pin "2") (pinfunction "2_2") (pintype "passive"))
      (node (ref "C27") (pin "2") (pinfunction "2_2") (pintype "passive"))
      (node (ref "C29") (pin "2") (pinfunction "2_2") (pintype "passive"))
      (node (ref "C5") (pin "2") (pinfunction "2_2") (pintype "passive"))
      (node (ref "C98") (pin "1") (pinfunction "1_1") (pintype "passive"))
      (node (ref "C99") (pin "2") (pinfunction "2_2") (pintype "passive"))
      (node (ref "D3") (pin "2") (pinfunction "A_2") (pintype "passive"))
      (node (ref "IC4") (pin "3") (pinfunction "IN_3") (pintype "input"))
      (node (ref "L7") (pin "2") (pinfunction "2_2") (pintype "passive"))
      (node (ref "R106") (pin "2") (pinfunction "2_2") (pintype "passive"))
      (node (ref "R62") (pin "1") (pinfunction "1_1") (pintype "passive"))
      (node (ref "U1") (pin "A13") (pinfunction "VCCIO_0_A13") (pintype "power_in"))
      (node (ref "U1") (pin "A3") (pinfunction "VCCIO_0_A3") (pintype "power_in"))
      (node (ref "U1") (pin "A8") (pinfunction "VCCIO_0_A8") (pintype "power_in"))
      (node (ref "U1") (pin "C15") (pinfunction "VCCIO_1_C15") (pintype "power_in"))
      (node (ref "U1") (pin "F8") (pinfunction "VCCIO_0_F8") (pintype "power_in"))
      (node (ref "U1") (pin "H10") (pinfunction "VCCIO_1_H10") (pintype "power_in"))
      (node (ref "U1") (pin "H15") (pinfunction "VCCIO_1_H15") (pintype "power_in"))
      (node (ref "U1") (pin "K8") (pinfunction "VCCIO_2_K8") (pintype "power_in"))
      (node (ref "U1") (pin "N13") (pinfunction "VCC_SPI_N13") (pintype "power_in"))
      (node (ref "U1") (pin "N15") (pinfunction "VCCIO_1_N15") (pintype "power_in"))
      (node (ref "U1") (pin "P3") (pinfunction "VCCIO_2_P3") (pintype "power_in"))
      (node (ref "U1") (pin "R13") (pinfunction "VCCIO_2_R13") (pintype "power_in"))
      (node (ref "U1") (pin "R8") (pinfunction "VCCIO_2_R8") (pintype "power_in"))
    )
    (net (code "45") (name "P3V3MP") (class "Default")
      (node (ref "B7") (pin "1") (pinfunction "1_1") (pintype "bidirectional"))
      (node (ref "C34") (pin "2") (pinfunction "2_2") (pintype "passive"))
      (node (ref "C35") (pin "2") (pinfunction "2_2") (pintype "passive"))
      (node (ref "IC2") (pin "8") (pinfunction "+VS_8") (pintype "power_in"))
      (node (ref "IC3") (pin "8") (pinfunction "+VS_8") (pintype "power_in"))
      (node (ref "JP2") (pin "2") (pinfunction "E2_2") (pintype "passive"))
      (node (ref "R164") (pin "1") (pinfunction "1_1") (pintype "passive"))
      (node (ref "R166") (pin "1") (pinfunction "1_1") (pintype "passive"))
      (node (ref "R2") (pin "2") (pinfunction "2_2") (pintype "passive"))
      (node (ref "R44") (pin "2") (pinfunction "2_2") (pintype "passive"))
    )
    (net (code "46") (name "P5V0") (class "Default")
      (node (ref "B5") (pin "1") (pinfunction "1_1") (pintype "bidirectional"))
      (node (ref "C244") (pin "2") (pinfunction "2_2") (pintype "passive"))
      (node (ref "C245") (pin "2") (pinfunction "2_2") (pintype "passive"))
      (node (ref "C246") (pin "2") (pinfunction "2_2") (pintype "passive"))
      (node (ref "C247") (pin "2") (pinfunction "2_2") (pintype "passive"))
      (node (ref "C252") (pin "2") (pinfunction "2_2") (pintype "passive"))
      (node (ref "C257") (pin "2") (pinfunction "2_2") (pintype "passive"))
      (node (ref "C97") (pin "2") (pinfunction "2_2") (pintype "passive"))
      (node (ref "IC25") (pin "2") (pinfunction "EN_2") (pintype "input"))
      (node (ref "IC25") (pin "3") (pinfunction "VIN_3") (pintype "input"))
      (node (ref "IC87") (pin "12") (pinfunction "VOUT_12") (pintype "power_in"))
      (node (ref "IC87") (pin "13") (pinfunction "VOUT_13") (pintype "power_in"))
      (node (ref "IC87") (pin "14") (pinfunction "VOUT_14") (pintype "power_in"))
      (node (ref "IC87") (pin "15") (pinfunction "VOUT_15") (pintype "power_in"))
      (node (ref "IC87") (pin "16") (pinfunction "VOUT_16") (pintype "power_in"))
      (node (ref "IC87") (pin "17") (pinfunction "VOUT_17") (pintype "power_in"))
      (node (ref "IC87") (pin "18") (pinfunction "VOUT_18") (pintype "power_in"))
      (node (ref "IC87") (pin "19") (pinfunction "VOUT_19") (pintype "power_in"))
      (node (ref "IC87") (pin "20") (pinfunction "VOUT_20") (pintype "power_in"))
      (node (ref "IC87") (pin "21") (pinfunction "VOUT_21") (pintype "power_in"))
      (node (ref "IC90") (pin "2") (pinfunction "EN_2") (pintype "input"))
      (node (ref "IC90") (pin "3") (pinfunction "VIN_3") (pintype "input"))
      (node (ref "R105") (pin "2") (pinfunction "2_2") (pintype "passive"))
      (node (ref "R367") (pin "2") (pinfunction "2_2") (pintype "passive"))
    )
    (net (code "47") (name "P12V0") (class "Default")
      (node (ref "B8") (pin "1") (pinfunction "1_1") (pintype "bidirectional"))
      (node (ref "C249") (pin "2") (pinfunction "2_2") (pintype "passive"))
      (node (ref "C250") (pin "2") (pinfunction "2_2") (pintype "passive"))
      (node (ref "C251") (pin "2") (pinfunction "2_2") (pintype "passive"))
      (node (ref "C84") (pin "1") (pinfunction "1_1") (pintype "passive"))
      (node (ref "FL1") (pin "2") (pinfunction "CB_2") (pintype "passive"))
      (node (ref "IC87") (pin "1") (pinfunction "PVIN_1") (pintype "power_in"))
      (node (ref "IC87") (pin "2") (pinfunction "PVIN_2") (pintype "power_in"))
      (node (ref "IC87") (pin "39") (pinfunction "VIN_39") (pintype "power_in"))
      (node (ref "IC87") (pin "52") (pinfunction "PVIN_52") (pintype "power_in"))
      (node (ref "R98") (pin "2") (pinfunction "2_2") (pintype "passive"))
    )
    (net (code "48") (name "P12V0F") (class "Default")
      (node (ref "FL1") (pin "1") (pinfunction "B_1") (pintype "passive"))
      (node (ref "J6") (pin "3") (pinfunction "3_3") (pintype "bidirectional"))
      (node (ref "J8") (pin "3") (pinfunction "3_3") (pintype "bidirectional"))
      (node (ref "J8") (pin "4") (pinfunction "4_4") (pintype "bidirectional"))
    )
    (net (code "49") (name "unconnected-(IC25-NC-Pad1)") (class "Default")
      (node (ref "IC25") (pin "1") (pinfunction "NC_1") (pintype "passive"))
    )
    (net (code "50") (name "unconnected-(IC87-NC-Pad23)") (class "Default")
      (node (ref "IC87") (pin "23") (pinfunction "NC_23") (pintype "passive+no_connect"))
    )
    (net (code "51") (name "unconnected-(IC87-NC-Pad24)") (class "Default")
      (node (ref "IC87") (pin "24") (pinfunction "NC_24") (pintype "passive+no_connect"))
    )
    (net (code "52") (name "unconnected-(IC87-NC-Pad25)") (class "Default")
      (node (ref "IC87") (pin "25") (pinfunction "NC_25") (pintype "passive+no_connect"))
    )
    (net (code "53") (name "unconnected-(IC87-NC-Pad27)") (class "Default")
      (node (ref "IC87") (pin "27") (pinfunction "NC_27") (pintype "passive+no_connect"))
    )
    (net (code "54") (name "unconnected-(IC87-NC-Pad28)") (class "Default")
      (node (ref "IC87") (pin "28") (pinfunction "NC_28") (pintype "passive+no_connect"))
    )
    (net (code "55") (name "unconnected-(IC87-NC-Pad29)") (class "Default")
      (node (ref "IC87") (pin "29") (pinfunction "NC_29") (pintype "passive+no_connect"))
    )
    (net (code "56") (name "unconnected-(IC87-NC-Pad30)") (class "Default")
      (node (ref "IC87") (pin "30") (pinfunction "NC_30") (pintype "passive+no_connect"))
    )
    (net (code "57") (name "unconnected-(IC87-NC-Pad32)") (class "Default")
      (node (ref "IC87") (pin "32") (pinfunction "NC_32") (pintype "passive+no_connect"))
    )
    (net (code "58") (name "unconnected-(IC87-NC-Pad33)") (class "Default")
      (node (ref "IC87") (pin "33") (pinfunction "NC_33") (pintype "passive+no_connect"))
    )
    (net (code "59") (name "unconnected-(IC87-NC-Pad34)") (class "Default")
      (node (ref "IC87") (pin "34") (pinfunction "NC_34") (pintype "passive+no_connect"))
    )
    (net (code "60") (name "unconnected-(IC87-NC-Pad40)") (class "Default")
      (node (ref "IC87") (pin "40") (pinfunction "NC_40") (pintype "passive+no_connect"))
    )
    (net (code "61") (name "unconnected-(IC87-NC-Pad41)") (class "Default")
      (node (ref "IC87") (pin "41") (pinfunction "NC_41") (pintype "passive+no_connect"))
    )
    (net (code "62") (name "unconnected-(IC90-NC-Pad1)") (class "Default")
      (node (ref "IC90") (pin "1") (pinfunction "NC_1") (pintype "passive"))
    )
    (net (code "63") (name "unconnected-(J6-Pad2)") (class "Default")
      (node (ref "J6") (pin "2") (pinfunction "2_2") (pintype "bidirectional"))
    )
  )
)
